# BigPieEVSE_EASYEDA.net
KiCad netlist of a schematic drawn in EasyEDA
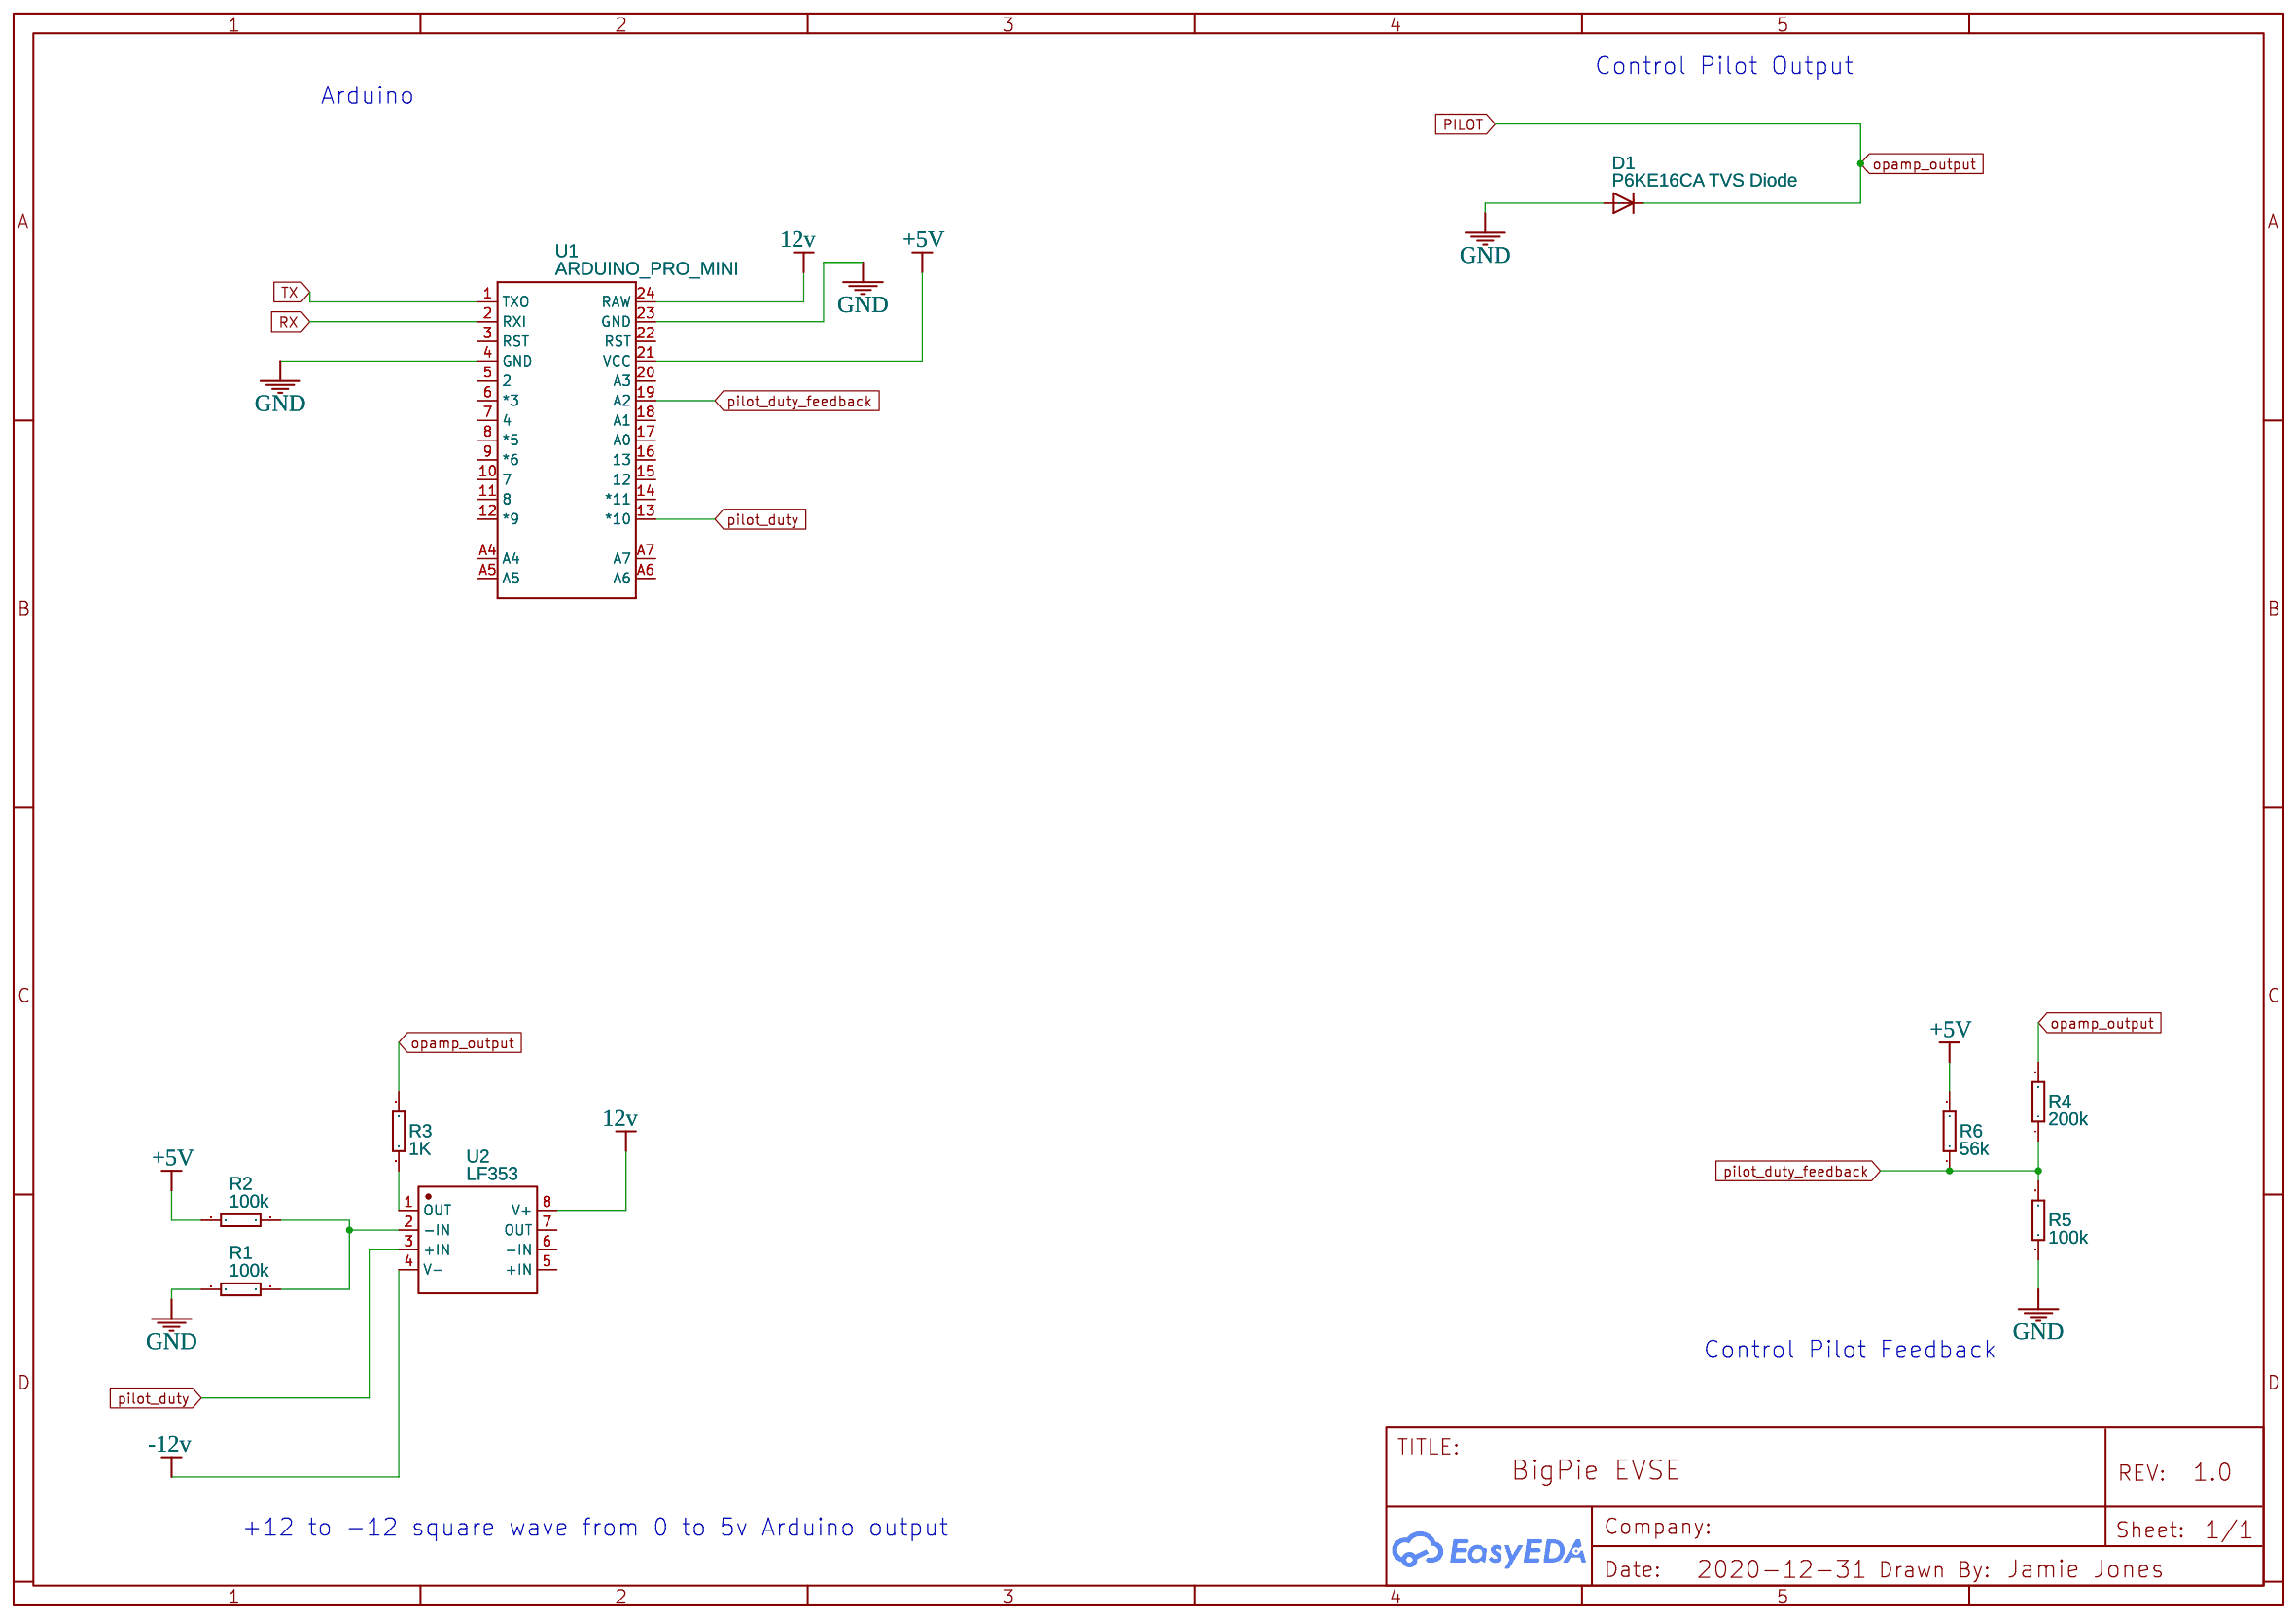
[diagram p0: schematic sheet]

(export (version "E")
  (design (tool "Eeschema 10.0.6"))
  (components
    (comp (ref "D1") (value "P6KE16CA TVS Diode") (libsource (lib "") (part "DIODE")))
    (comp (ref "R1") (value "100k") (libsource (lib "") (part "RESISTOR_1")))
    (comp (ref "R2") (value "100k") (libsource (lib "") (part "RESISTOR_1")))
    (comp (ref "R3") (value "1K") (libsource (lib "") (part "RESISTOR")))
    (comp (ref "R4") (value "200k") (libsource (lib "") (part "RESISTOR")))
    (comp (ref "R5") (value "100k") (libsource (lib "") (part "RESISTOR")))
    (comp (ref "R6") (value "56k") (libsource (lib "") (part "RESISTOR")))
    (comp (ref "U1") (value "ARDUINO_PRO_MINI") (libsource (lib "") (part "ARDUINO_PRO_MINI")))
    (comp (ref "U2") (value "LF353") (libsource (lib "") (part "LF353")))
  )
  (nets
    (net (code "1") (name "+5V") (class "Default")
      (node (ref "R2") (pin "2") (pinfunction "2_2") (pintype "unspecified"))
      (node (ref "R6") (pin "2") (pinfunction "2_2") (pintype "unspecified"))
      (node (ref "U1") (pin "21") (pinfunction "VCC_21") (pintype "unspecified"))
    )
    (net (code "2") (name "-12v") (class "Default")
      (node (ref "U2") (pin "4") (pinfunction "V-_4") (pintype "unspecified"))
    )
    (net (code "3") (name "12v") (class "Default")
      (node (ref "U1") (pin "24") (pinfunction "RAW_24") (pintype "unspecified"))
      (node (ref "U2") (pin "8") (pinfunction "V+_8") (pintype "unspecified"))
    )
    (net (code "4") (name "GND") (class "Default")
      (node (ref "D1") (pin "A") (pinfunction "A_A") (pintype "unspecified"))
      (node (ref "R1") (pin "2") (pinfunction "2_2") (pintype "unspecified"))
      (node (ref "R5") (pin "1") (pinfunction "1_1") (pintype "unspecified"))
      (node (ref "U1") (pin "23") (pinfunction "GND_23") (pintype "unspecified"))
      (node (ref "U1") (pin "4") (pinfunction "GND_4") (pintype "unspecified"))
    )
    (net (code "5") (name "Net-(R1-Pad1)") (class "Default")
      (node (ref "R1") (pin "1") (pinfunction "1_1") (pintype "unspecified"))
      (node (ref "R2") (pin "1") (pinfunction "1_1") (pintype "unspecified"))
      (node (ref "U2") (pin "2") (pinfunction "-IN_2") (pintype "unspecified"))
    )
    (net (code "6") (name "Net-(R3-Pad1)") (class "Default")
      (node (ref "R3") (pin "1") (pinfunction "1_1") (pintype "unspecified"))
      (node (ref "U2") (pin "1") (pinfunction "OUT_1") (pintype "unspecified"))
    )
    (net (code "7") (name "PILOT") (class "Default")
      (node (ref "D1") (pin "C") (pinfunction "C_C") (pintype "unspecified"))
      (node (ref "R3") (pin "2") (pinfunction "2_2") (pintype "unspecified"))
      (node (ref "R4") (pin "2") (pinfunction "2_2") (pintype "unspecified"))
    )
    (net (code "8") (name "RX") (class "Default")
      (node (ref "U1") (pin "2") (pinfunction "RXI_2") (pintype "unspecified"))
    )
    (net (code "9") (name "TX") (class "Default")
      (node (ref "U1") (pin "1") (pinfunction "TXO_1") (pintype "unspecified"))
    )
    (net (code "10") (name "pilot_duty") (class "Default")
      (node (ref "U1") (pin "13") (pinfunction "*10_13") (pintype "unspecified"))
      (node (ref "U2") (pin "3") (pinfunction "+IN_3") (pintype "unspecified"))
    )
    (net (code "11") (name "pilot_duty_feedback") (class "Default")
      (node (ref "R4") (pin "1") (pinfunction "1_1") (pintype "unspecified"))
      (node (ref "R5") (pin "2") (pinfunction "2_2") (pintype "unspecified"))
      (node (ref "R6") (pin "1") (pinfunction "1_1") (pintype "unspecified"))
      (node (ref "U1") (pin "19") (pinfunction "A2_19") (pintype "unspecified"))
    )
    (net (code "12") (name "unconnected-(U1-*3-Pad6)") (class "Default")
      (node (ref "U1") (pin "6") (pinfunction "*3_6") (pintype "unspecified"))
    )
    (net (code "13") (name "unconnected-(U1-*5-Pad8)") (class "Default")
      (node (ref "U1") (pin "8") (pinfunction "*5_8") (pintype "unspecified"))
    )
    (net (code "14") (name "unconnected-(U1-*6-Pad9)") (class "Default")
      (node (ref "U1") (pin "9") (pinfunction "*6_9") (pintype "unspecified"))
    )
    (net (code "15") (name "unconnected-(U1-*9-Pad12)") (class "Default")
      (node (ref "U1") (pin "12") (pinfunction "*9_12") (pintype "unspecified"))
    )
    (net (code "16") (name "unconnected-(U1-*11-Pad14)") (class "Default")
      (node (ref "U1") (pin "14") (pinfunction "*11_14") (pintype "unspecified"))
    )
    (net (code "17") (name "unconnected-(U1-2-Pad5)") (class "Default")
      (node (ref "U1") (pin "5") (pinfunction "2_5") (pintype "unspecified"))
    )
    (net (code "18") (name "unconnected-(U1-4-Pad7)") (class "Default")
      (node (ref "U1") (pin "7") (pinfunction "4_7") (pintype "unspecified"))
    )
    (net (code "19") (name "unconnected-(U1-7-Pad10)") (class "Default")
      (node (ref "U1") (pin "10") (pinfunction "7_10") (pintype "unspecified"))
    )
    (net (code "20") (name "unconnected-(U1-8-Pad11)") (class "Default")
      (node (ref "U1") (pin "11") (pinfunction "8_11") (pintype "unspecified"))
    )
    (net (code "21") (name "unconnected-(U1-12-Pad15)") (class "Default")
      (node (ref "U1") (pin "15") (pinfunction "12_15") (pintype "unspecified"))
    )
    (net (code "22") (name "unconnected-(U1-13-Pad16)") (class "Default")
      (node (ref "U1") (pin "16") (pinfunction "13_16") (pintype "unspecified"))
    )
    (net (code "23") (name "unconnected-(U1-A0-Pad17)") (class "Default")
      (node (ref "U1") (pin "17") (pinfunction "A0_17") (pintype "unspecified"))
    )
    (net (code "24") (name "unconnected-(U1-A1-Pad18)") (class "Default")
      (node (ref "U1") (pin "18") (pinfunction "A1_18") (pintype "unspecified"))
    )
    (net (code "25") (name "unconnected-(U1-A3-Pad20)") (class "Default")
      (node (ref "U1") (pin "20") (pinfunction "A3_20") (pintype "unspecified"))
    )
    (net (code "26") (name "unconnected-(U1-PadA4)") (class "Default")
      (node (ref "U1") (pin "A4") (pinfunction "A4_A4") (pintype "unspecified"))
    )
    (net (code "27") (name "unconnected-(U1-PadA5)") (class "Default")
      (node (ref "U1") (pin "A5") (pinfunction "A5_A5") (pintype "unspecified"))
    )
    (net (code "28") (name "unconnected-(U1-PadA6)") (class "Default")
      (node (ref "U1") (pin "A6") (pinfunction "A6_A6") (pintype "unspecified"))
    )
    (net (code "29") (name "unconnected-(U1-PadA7)") (class "Default")
      (node (ref "U1") (pin "A7") (pinfunction "A7_A7") (pintype "unspecified"))
    )
    (net (code "30") (name "unconnected-(U1-RST-Pad3)") (class "Default")
      (node (ref "U1") (pin "3") (pinfunction "RST_3") (pintype "unspecified"))
    )
    (net (code "31") (name "unconnected-(U1-RST-Pad22)") (class "Default")
      (node (ref "U1") (pin "22") (pinfunction "RST_22") (pintype "unspecified"))
    )
    (net (code "32") (name "unconnected-(U2-+IN-Pad5)") (class "Default")
      (node (ref "U2") (pin "5") (pinfunction "+IN_5") (pintype "unspecified"))
    )
    (net (code "33") (name "unconnected-(U2--IN-Pad6)") (class "Default")
      (node (ref "U2") (pin "6") (pinfunction "-IN_6") (pintype "unspecified"))
    )
    (net (code "34") (name "unconnected-(U2-OUT-Pad7)") (class "Default")
      (node (ref "U2") (pin "7") (pinfunction "OUT_7") (pintype "unspecified"))
    )
  )
)
